# untitled.net
KiCad netlist of a schematic drawn in EAGLE
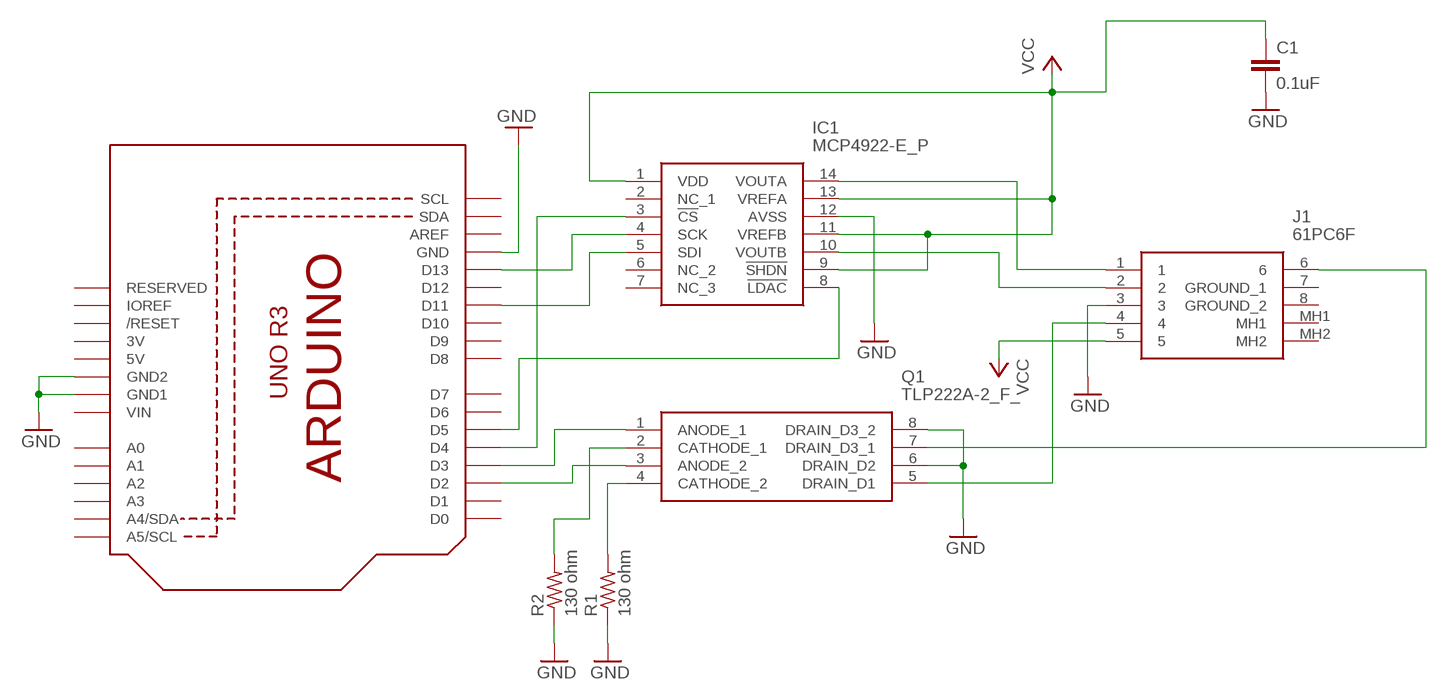
[diagram p0: schematic, sheet 1]

(export (version "E")
  (design (tool "Eeschema 10.0.6"))
  (components
    (comp (ref "C1")
      (value "0.1uF")
      (footprint "eagle-import:C050-024X044")
      (libsource (lib "eagle-import") (part "C-EU050-024X044"))
    )
    (comp (ref "IC1")
      (value "MCP4922-E_P")
      (footprint "eagle-import:DIP794W56P254L1905H432Q14N")
      (fields
        (field (name "MANUFACTURER_PART_NUMBER") "MCP4922-E/P")
        (field (name "MOUSER_PART_NUMBER") "579-MCP4922-E/P")
      )
      (libsource (lib "eagle-import") (part "MCP4922-E_P"))
    )
    (comp (ref "J1")
      (value "61PC6F")
      (footprint "eagle-import:61PC6F")
      (fields (field (name "MOUSER_PART_NUMBER") "502-61PC6F"))
      (libsource (lib "eagle-import") (part "61PC6F"))
    )
    (comp (ref "Q1")
      (value "TLP222A-2_F_")
      (footprint "eagle-import:DIP762W60P254L966H485Q8N")
      (fields
        (field (name "MANUFACTURER_PART_NUMBER") "TLP222A-2(F)")
        (field (name "MOUSER_PART_NUMBER") "757-TLP222A-2(F)")
      )
      (libsource (lib "eagle-import") (part "TLP222A-2_F_"))
    )
    (comp (ref "R1")
      (value "130 ohm")
      (footprint "eagle-import:0207_7")
      (libsource (lib "eagle-import") (part "R-US_0207/7"))
    )
    (comp (ref "R2")
      (value "130 ohm")
      (footprint "eagle-import:0207_7")
      (libsource (lib "eagle-import") (part "R-US_0207/7"))
    )
    (comp (ref "U1")
      (value "ARDUINOR3-BPLACE")
      (footprint "eagle-import:ARDUINOR3-BPLACE")
      (libsource (lib "eagle-import") (part "ARDUINOR3-BPLACE"))
    )
  )
  (nets
    (net (code "1") (name "/3V") (class "Default")
      (node (ref "U1") (pin "3V") (pinfunction "3V_3V") (pintype "power_in"))
    )
    (net (code "2") (name "/5V") (class "Default")
      (node (ref "U1") (pin "5V") (pinfunction "5V_5V") (pintype "power_in"))
    )
    (net (code "3") (name "/VIN") (class "Default")
      (node (ref "U1") (pin "VIN") (pinfunction "VIN_VIN") (pintype "power_in"))
    )
    (net (code "4") (name "GND") (class "Default")
      (node (ref "C1") (pin "2") (pinfunction "2_2") (pintype "passive"))
      (node (ref "IC1") (pin "12") (pinfunction "AVSS_12") (pintype "bidirectional"))
      (node (ref "J1") (pin "3") (pinfunction "3_3") (pintype "bidirectional"))
      (node (ref "Q1") (pin "6") (pinfunction "DRAIN_D2_6") (pintype "bidirectional"))
      (node (ref "Q1") (pin "8") (pinfunction "DRAIN_D3_2_8") (pintype "bidirectional"))
      (node (ref "R1") (pin "1") (pinfunction "1_1") (pintype "passive"))
      (node (ref "R2") (pin "1") (pinfunction "1_1") (pintype "passive"))
      (node (ref "U1") (pin "GND") (pinfunction "GND_GND") (pintype "power_in"))
      (node (ref "U1") (pin "GND1") (pinfunction "GND1_GND1") (pintype "power_in"))
      (node (ref "U1") (pin "GND2") (pinfunction "GND2_GND2") (pintype "power_in"))
    )
    (net (code "5") (name "Net-(IC1-SCK)") (class "Default")
      (node (ref "IC1") (pin "4") (pinfunction "SCK_4") (pintype "bidirectional"))
      (node (ref "U1") (pin "D13") (pinfunction "D13_D13") (pintype "bidirectional"))
    )
    (net (code "6") (name "Net-(IC1-SDI)") (class "Default")
      (node (ref "IC1") (pin "5") (pinfunction "SDI_5") (pintype "bidirectional"))
      (node (ref "U1") (pin "D11") (pinfunction "D11_D11") (pintype "bidirectional"))
    )
    (net (code "7") (name "Net-(IC1-VOUTA)") (class "Default")
      (node (ref "IC1") (pin "14") (pinfunction "VOUTA_14") (pintype "bidirectional"))
      (node (ref "J1") (pin "1") (pinfunction "1_1") (pintype "bidirectional"))
    )
    (net (code "8") (name "Net-(IC1-VOUTB)") (class "Default")
      (node (ref "IC1") (pin "10") (pinfunction "VOUTB_10") (pintype "bidirectional"))
      (node (ref "J1") (pin "2") (pinfunction "2_2") (pintype "bidirectional"))
    )
    (net (code "9") (name "Net-(IC1-~{CS})") (class "Default")
      (node (ref "IC1") (pin "3") (pinfunction "~{CS}_3") (pintype "bidirectional"))
      (node (ref "U1") (pin "D4") (pinfunction "D4_D4") (pintype "bidirectional"))
    )
    (net (code "10") (name "Net-(IC1-~{LDAC})") (class "Default")
      (node (ref "IC1") (pin "8") (pinfunction "~{LDAC}_8") (pintype "bidirectional"))
      (node (ref "U1") (pin "D5") (pinfunction "D5_D5") (pintype "bidirectional"))
    )
    (net (code "11") (name "Net-(Q1-ANODE_1)") (class "Default")
      (node (ref "Q1") (pin "1") (pinfunction "ANODE_1_1") (pintype "bidirectional"))
      (node (ref "U1") (pin "D3") (pinfunction "D3_D3") (pintype "bidirectional"))
    )
    (net (code "12") (name "Net-(Q1-ANODE_2)") (class "Default")
      (node (ref "Q1") (pin "3") (pinfunction "ANODE_2_3") (pintype "bidirectional"))
      (node (ref "U1") (pin "D2") (pinfunction "D2_D2") (pintype "bidirectional"))
    )
    (net (code "13") (name "Net-(Q1-CATHODE_1)") (class "Default")
      (node (ref "Q1") (pin "2") (pinfunction "CATHODE_1_2") (pintype "bidirectional"))
      (node (ref "R2") (pin "2") (pinfunction "2_2") (pintype "passive"))
    )
    (net (code "14") (name "Net-(Q1-CATHODE_2)") (class "Default")
      (node (ref "Q1") (pin "4") (pinfunction "CATHODE_2_4") (pintype "bidirectional"))
      (node (ref "R1") (pin "2") (pinfunction "2_2") (pintype "passive"))
    )
    (net (code "15") (name "Net-(Q1-DRAIN_D1)") (class "Default")
      (node (ref "J1") (pin "4") (pinfunction "4_4") (pintype "bidirectional"))
      (node (ref "Q1") (pin "5") (pinfunction "DRAIN_D1_5") (pintype "bidirectional"))
    )
    (net (code "16") (name "Net-(Q1-DRAIN_D3_1)") (class "Default")
      (node (ref "J1") (pin "6") (pinfunction "6_6") (pintype "bidirectional"))
      (node (ref "Q1") (pin "7") (pinfunction "DRAIN_D3_1_7") (pintype "bidirectional"))
    )
    (net (code "17") (name "VCC") (class "Default")
      (node (ref "C1") (pin "1") (pinfunction "1_1") (pintype "passive"))
      (node (ref "IC1") (pin "1") (pinfunction "VDD_1") (pintype "bidirectional"))
      (node (ref "IC1") (pin "11") (pinfunction "VREFB_11") (pintype "bidirectional"))
      (node (ref "IC1") (pin "13") (pinfunction "VREFA_13") (pintype "bidirectional"))
      (node (ref "IC1") (pin "9") (pinfunction "~{SHDN}_9") (pintype "bidirectional"))
      (node (ref "J1") (pin "5") (pinfunction "5_5") (pintype "bidirectional"))
    )
    (net (code "18") (name "unconnected-(IC1-NC_1-Pad2)") (class "Default")
      (node (ref "IC1") (pin "2") (pinfunction "NC_1_2") (pintype "bidirectional"))
    )
    (net (code "19") (name "unconnected-(IC1-NC_2-Pad6)") (class "Default")
      (node (ref "IC1") (pin "6") (pinfunction "NC_2_6") (pintype "bidirectional"))
    )
    (net (code "20") (name "unconnected-(IC1-NC_3-Pad7)") (class "Default")
      (node (ref "IC1") (pin "7") (pinfunction "NC_3_7") (pintype "bidirectional"))
    )
    (net (code "21") (name "unconnected-(J1-GROUND_1-Pad7)") (class "Default")
      (node (ref "J1") (pin "7") (pinfunction "GROUND_1_7") (pintype "bidirectional"))
    )
    (net (code "22") (name "unconnected-(J1-GROUND_2-Pad8)") (class "Default")
      (node (ref "J1") (pin "8") (pinfunction "GROUND_2_8") (pintype "bidirectional"))
    )
    (net (code "23") (name "unconnected-(J1-PadMH1)") (class "Default")
      (node (ref "J1") (pin "MH1") (pinfunction "MH1_MH1") (pintype "bidirectional"))
    )
    (net (code "24") (name "unconnected-(J1-PadMH2)") (class "Default")
      (node (ref "J1") (pin "MH2") (pinfunction "MH2_MH2") (pintype "bidirectional"))
    )
    (net (code "25") (name "unconnected-(U1-A4{slash}SDA-PadA4)") (class "Default")
      (node (ref "U1") (pin "A4") (pinfunction "A4/SDA_A4") (pintype "bidirectional"))
    )
    (net (code "26") (name "unconnected-(U1-A5{slash}SCL-PadA5)") (class "Default")
      (node (ref "U1") (pin "A5") (pinfunction "A5/SCL_A5") (pintype "bidirectional"))
    )
    (net (code "27") (name "unconnected-(U1-PadA0)") (class "Default")
      (node (ref "U1") (pin "A0") (pinfunction "A0_A0") (pintype "bidirectional"))
    )
    (net (code "28") (name "unconnected-(U1-PadA1)") (class "Default")
      (node (ref "U1") (pin "A1") (pinfunction "A1_A1") (pintype "bidirectional"))
    )
    (net (code "29") (name "unconnected-(U1-PadA2)") (class "Default")
      (node (ref "U1") (pin "A2") (pinfunction "A2_A2") (pintype "bidirectional"))
    )
    (net (code "30") (name "unconnected-(U1-PadA3)") (class "Default")
      (node (ref "U1") (pin "A3") (pinfunction "A3_A3") (pintype "bidirectional"))
    )
    (net (code "31") (name "unconnected-(U1-PadAREF)") (class "Default")
      (node (ref "U1") (pin "AREF") (pinfunction "AREF_AREF") (pintype "bidirectional"))
    )
    (net (code "32") (name "unconnected-(U1-PadD0)") (class "Default")
      (node (ref "U1") (pin "D0") (pinfunction "D0_D0") (pintype "bidirectional"))
    )
    (net (code "33") (name "unconnected-(U1-PadD1)") (class "Default")
      (node (ref "U1") (pin "D1") (pinfunction "D1_D1") (pintype "bidirectional"))
    )
    (net (code "34") (name "unconnected-(U1-PadD6)") (class "Default")
      (node (ref "U1") (pin "D6") (pinfunction "D6_D6") (pintype "bidirectional"))
    )
    (net (code "35") (name "unconnected-(U1-PadD7)") (class "Default")
      (node (ref "U1") (pin "D7") (pinfunction "D7_D7") (pintype "bidirectional"))
    )
    (net (code "36") (name "unconnected-(U1-PadD8)") (class "Default")
      (node (ref "U1") (pin "D8") (pinfunction "D8_D8") (pintype "bidirectional"))
    )
    (net (code "37") (name "unconnected-(U1-PadD9)") (class "Default")
      (node (ref "U1") (pin "D9") (pinfunction "D9_D9") (pintype "bidirectional"))
    )
    (net (code "38") (name "unconnected-(U1-PadD10)") (class "Default")
      (node (ref "U1") (pin "D10") (pinfunction "D10_D10") (pintype "bidirectional"))
    )
    (net (code "39") (name "unconnected-(U1-PadD12)") (class "Default")
      (node (ref "U1") (pin "D12") (pinfunction "D12_D12") (pintype "bidirectional"))
    )
    (net (code "40") (name "unconnected-(U1-PadIOREF)") (class "Default")
      (node (ref "U1") (pin "IOREF") (pinfunction "IOREF_IOREF") (pintype "output"))
    )
    (net (code "41") (name "unconnected-(U1-PadRESERVED)") (class "Default")
      (node (ref "U1") (pin "RESERVED") (pinfunction "RESERVED_RESERVED") (pintype "no_connect"))
    )
    (net (code "42") (name "unconnected-(U1-PadSCL)") (class "Default")
      (node (ref "U1") (pin "SCL") (pinfunction "SCL_SCL") (pintype "bidirectional"))
    )
    (net (code "43") (name "unconnected-(U1-PadSDA)") (class "Default")
      (node (ref "U1") (pin "SDA") (pinfunction "SDA_SDA") (pintype "bidirectional"))
    )
    (net (code "44") (name "unconnected-(U1-{slash}RESET-PadRESET)") (class "Default")
      (node (ref "U1") (pin "RESET") (pinfunction "/RESET_RESET") (pintype "bidirectional"))
    )
  )
)
